# Aux_Board_V4.net
KiCad netlist of a schematic drawn in EAGLE
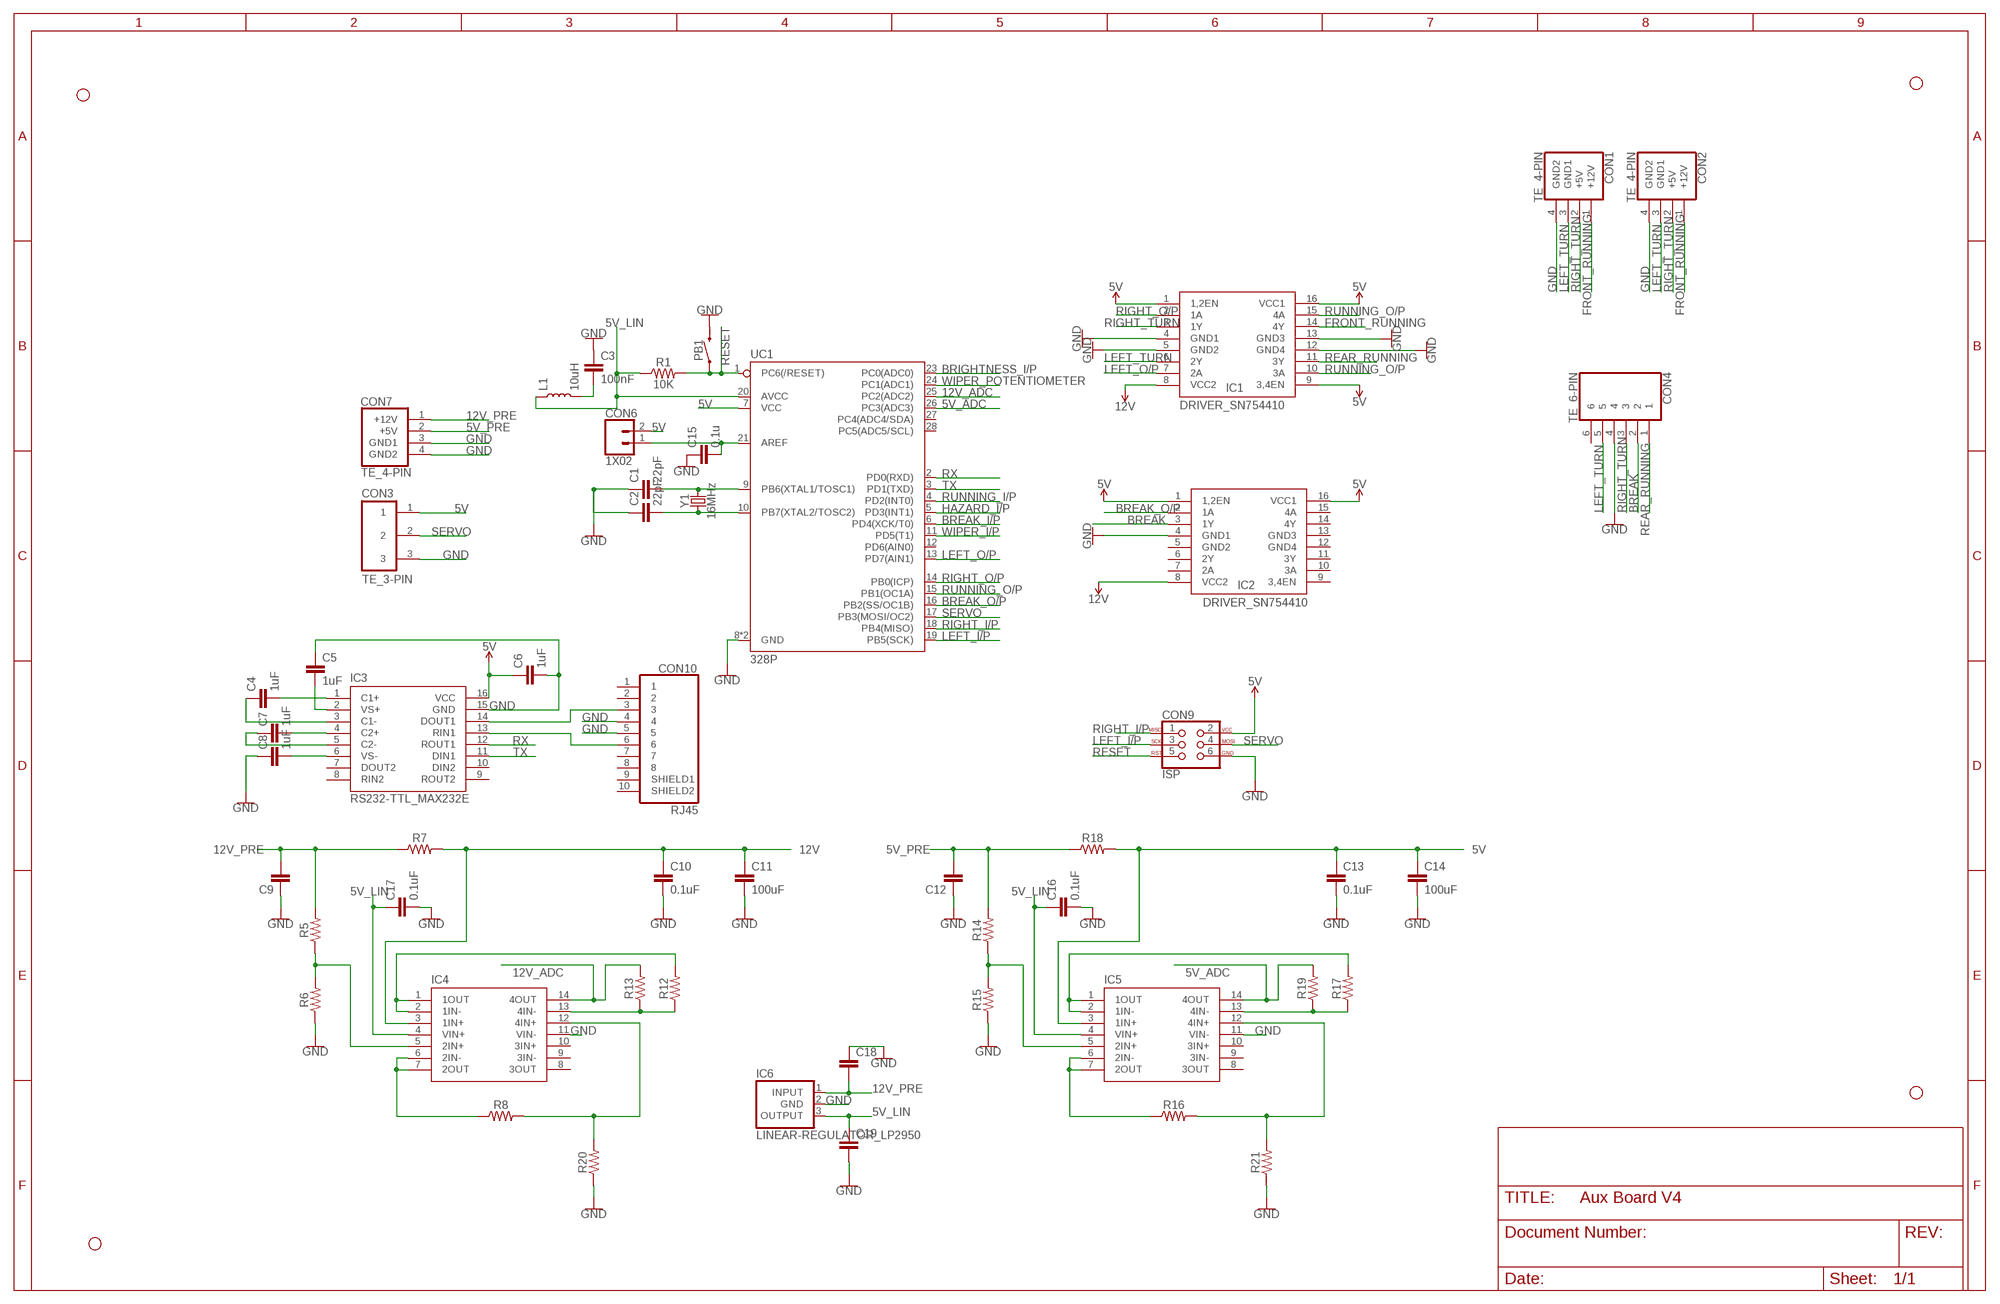
[diagram p0: schematic, sheet 1]

(export (version "E")
  (design (tool "Eeschema 10.0.6"))
  (components
    (comp (ref "C1")
      (value "22pF")
      (footprint "eagle-import:0805")
      (libsource (lib "eagle-import") (part "CAPACITOR_0805"))
    )
    (comp (ref "C2")
      (value "22pF")
      (footprint "eagle-import:0805")
      (libsource (lib "eagle-import") (part "CAPACITOR_0805"))
    )
    (comp (ref "C3")
      (value "100nF")
      (footprint "eagle-import:0805")
      (libsource (lib "eagle-import") (part "CAPACITOR_0805"))
    )
    (comp (ref "C4")
      (value "1uF")
      (footprint "eagle-import:0805")
      (libsource (lib "eagle-import") (part "CAPACITOR_0805"))
    )
    (comp (ref "C5")
      (value "1uF")
      (footprint "eagle-import:0805")
      (libsource (lib "eagle-import") (part "CAPACITOR_0805"))
    )
    (comp (ref "C6")
      (value "1uF")
      (footprint "eagle-import:0805")
      (libsource (lib "eagle-import") (part "CAPACITOR_0805"))
    )
    (comp (ref "C7")
      (value "1uF")
      (footprint "eagle-import:0805")
      (libsource (lib "eagle-import") (part "CAPACITOR_0805"))
    )
    (comp (ref "C8")
      (value "1uF")
      (footprint "eagle-import:0805")
      (libsource (lib "eagle-import") (part "CAPACITOR_0805"))
    )
    (comp (ref "C9")
      (value "CAPACITOR_0805")
      (footprint "eagle-import:0805")
      (libsource (lib "eagle-import") (part "CAPACITOR_0805"))
    )
    (comp (ref "C10")
      (value "0.1uF")
      (footprint "eagle-import:0805")
      (libsource (lib "eagle-import") (part "CAPACITOR_0805"))
    )
    (comp (ref "C11")
      (value "100uF")
      (footprint "eagle-import:0805")
      (libsource (lib "eagle-import") (part "CAPACITOR_0805"))
    )
    (comp (ref "C12")
      (value "CAPACITOR_0805")
      (footprint "eagle-import:0805")
      (libsource (lib "eagle-import") (part "CAPACITOR_0805"))
    )
    (comp (ref "C13")
      (value "0.1uF")
      (footprint "eagle-import:0805")
      (libsource (lib "eagle-import") (part "CAPACITOR_0805"))
    )
    (comp (ref "C14")
      (value "100uF")
      (footprint "eagle-import:0805")
      (libsource (lib "eagle-import") (part "CAPACITOR_0805"))
    )
    (comp (ref "C15")
      (value "0.1u")
      (footprint "eagle-import:0805")
      (libsource (lib "eagle-import") (part "CAPACITOR_0805"))
    )
    (comp (ref "C16")
      (value "0.1uF")
      (footprint "eagle-import:0805")
      (libsource (lib "eagle-import") (part "CAPACITOR_0805"))
    )
    (comp (ref "C17")
      (value "0.1uF")
      (footprint "eagle-import:0805")
      (libsource (lib "eagle-import") (part "CAPACITOR_0805"))
    )
    (comp (ref "C18")
      (value "CAPACITOR_0805")
      (footprint "eagle-import:0805")
      (libsource (lib "eagle-import") (part "CAPACITOR_0805"))
    )
    (comp (ref "C19")
      (value "CAPACITOR_0805")
      (footprint "eagle-import:0805")
      (libsource (lib "eagle-import") (part "CAPACITOR_0805"))
    )
    (comp (ref "CON1")
      (value "TE_4-PIN")
      (footprint "eagle-import:TE_4-PIN")
      (libsource (lib "eagle-import") (part "TE_4-PIN"))
    )
    (comp (ref "CON2")
      (value "TE_4-PIN")
      (footprint "eagle-import:TE_4-PIN")
      (libsource (lib "eagle-import") (part "TE_4-PIN"))
    )
    (comp (ref "CON3")
      (value "TE_3-PIN")
      (footprint "eagle-import:TE_3-PIN")
      (libsource (lib "eagle-import") (part "TE_3-PIN"))
    )
    (comp (ref "CON4")
      (value "TE_6-PIN")
      (footprint "eagle-import:TE_6-PIN")
      (libsource (lib "eagle-import") (part "TE_6-PIN"))
    )
    (comp (ref "CON6")
      (value "1X02")
      (footprint "eagle-import:1X02")
      (libsource (lib "eagle-import") (part "1X02"))
    )
    (comp (ref "CON7")
      (value "TE_4-PIN")
      (footprint "eagle-import:TE_4-PIN")
      (libsource (lib "eagle-import") (part "TE_4-PIN"))
    )
    (comp (ref "CON9")
      (value "ISP")
      (footprint "eagle-import:ISP_CONNECTOR")
      (libsource (lib "eagle-import") (part "ISP"))
    )
    (comp (ref "CON10")
      (value "RJ45")
      (footprint "eagle-import:RJ45")
      (libsource (lib "eagle-import") (part "RJ45"))
    )
    (comp (ref "H1")
      (value "STAND-OFF")
      (footprint "eagle-import:STAND-OFF")
      (libsource (lib "eagle-import") (part "STAND-OFF"))
    )
    (comp (ref "H2")
      (value "STAND-OFF")
      (footprint "eagle-import:STAND-OFF")
      (libsource (lib "eagle-import") (part "STAND-OFF"))
    )
    (comp (ref "H3")
      (value "STAND-OFF")
      (footprint "eagle-import:STAND-OFF")
      (libsource (lib "eagle-import") (part "STAND-OFF"))
    )
    (comp (ref "H4")
      (value "STAND-OFF")
      (footprint "eagle-import:STAND-OFF")
      (libsource (lib "eagle-import") (part "STAND-OFF"))
    )
    (comp (ref "IC1")
      (value "DRIVER_SN754410")
      (footprint "eagle-import:DIP16")
      (libsource (lib "eagle-import") (part "DRIVER_SN754410"))
    )
    (comp (ref "IC2")
      (value "DRIVER_SN754410")
      (footprint "eagle-import:DIP16")
      (libsource (lib "eagle-import") (part "DRIVER_SN754410"))
    )
    (comp (ref "IC3")
      (value "RS232-TTL_MAX232E")
      (footprint "eagle-import:DIP16")
      (libsource (lib "eagle-import") (part "RS232-TTL_MAX232E"))
    )
    (comp (ref "IC4")
      (value "OP-AMP_QUAD")
      (footprint "eagle-import:DIP14")
      (libsource (lib "eagle-import") (part "OP-AMP_QUAD"))
    )
    (comp (ref "IC5")
      (value "OP-AMP_QUAD")
      (footprint "eagle-import:DIP14")
      (libsource (lib "eagle-import") (part "OP-AMP_QUAD"))
    )
    (comp (ref "IC6")
      (value "LINEAR-REGULATOR_LP2950")
      (footprint "eagle-import:TO92")
      (libsource (lib "eagle-import") (part "LINEAR-REGULATOR_LP2950"))
    )
    (comp (ref "L1")
      (value "10uH")
      (footprint "eagle-import:0805")
      (libsource (lib "eagle-import") (part "INDUCTOR_0805"))
    )
    (comp (ref "PB1")
      (value "PUSHBUTTON")
      (footprint "eagle-import:PUSHBUTTON")
      (libsource (lib "eagle-import") (part "PUSHBUTTON"))
    )
    (comp (ref "R1")
      (value "10K")
      (footprint "eagle-import:0805")
      (libsource (lib "eagle-import") (part "RESISTOR_0805"))
    )
    (comp (ref "R5")
      (value "RESISTOR_0805")
      (footprint "eagle-import:0805")
      (libsource (lib "eagle-import") (part "RESISTOR_0805"))
    )
    (comp (ref "R6")
      (value "RESISTOR_0805")
      (footprint "eagle-import:0805")
      (libsource (lib "eagle-import") (part "RESISTOR_0805"))
    )
    (comp (ref "R7")
      (value "RESISTOR_1210")
      (footprint "eagle-import:1210")
      (libsource (lib "eagle-import") (part "RESISTOR_1210"))
    )
    (comp (ref "R8")
      (value "RESISTOR_0805")
      (footprint "eagle-import:0805")
      (libsource (lib "eagle-import") (part "RESISTOR_0805"))
    )
    (comp (ref "R12")
      (value "RESISTOR_0805")
      (footprint "eagle-import:0805")
      (libsource (lib "eagle-import") (part "RESISTOR_0805"))
    )
    (comp (ref "R13")
      (value "RESISTOR_0805")
      (footprint "eagle-import:0805")
      (libsource (lib "eagle-import") (part "RESISTOR_0805"))
    )
    (comp (ref "R14")
      (value "RESISTOR_0805")
      (footprint "eagle-import:0805")
      (libsource (lib "eagle-import") (part "RESISTOR_0805"))
    )
    (comp (ref "R15")
      (value "RESISTOR_0805")
      (footprint "eagle-import:0805")
      (libsource (lib "eagle-import") (part "RESISTOR_0805"))
    )
    (comp (ref "R16")
      (value "RESISTOR_0805")
      (footprint "eagle-import:0805")
      (libsource (lib "eagle-import") (part "RESISTOR_0805"))
    )
    (comp (ref "R17")
      (value "RESISTOR_0805")
      (footprint "eagle-import:0805")
      (libsource (lib "eagle-import") (part "RESISTOR_0805"))
    )
    (comp (ref "R18")
      (value "RESISTOR_1210")
      (footprint "eagle-import:1210")
      (libsource (lib "eagle-import") (part "RESISTOR_1210"))
    )
    (comp (ref "R19")
      (value "RESISTOR_0805")
      (footprint "eagle-import:0805")
      (libsource (lib "eagle-import") (part "RESISTOR_0805"))
    )
    (comp (ref "R20")
      (value "RESISTOR_0805")
      (footprint "eagle-import:0805")
      (libsource (lib "eagle-import") (part "RESISTOR_0805"))
    )
    (comp (ref "R21")
      (value "RESISTOR_0805")
      (footprint "eagle-import:0805")
      (libsource (lib "eagle-import") (part "RESISTOR_0805"))
    )
    (comp (ref "UC1")
      (value "328P")
      (footprint "eagle-import:DIP28")
      (libsource (lib "eagle-import") (part "ATMEGA328P_DIP28"))
    )
    (comp (ref "Y1")
      (value "16MHz")
      (footprint "eagle-import:HC49US")
      (libsource (lib "eagle-import") (part "CRYSTAL-16MHZPTH-HC49US"))
    )
  )
  (nets
    (net (code "1") (name "/5V_ADC") (class "Default")
      (node (ref "IC5") (pin "14") (pinfunction "4OUT_14") (pintype "bidirectional"))
      (node (ref "R19") (pin "2") (pinfunction "2_2") (pintype "passive"))
      (node (ref "UC1") (pin "26") (pinfunction "PC3(ADC3)_26") (pintype "bidirectional"))
    )
    (net (code "2") (name "/5V_LIN") (class "Default")
      (node (ref "C16") (pin "1") (pinfunction "1_1") (pintype "passive"))
      (node (ref "C17") (pin "1") (pinfunction "1_1") (pintype "passive"))
      (node (ref "C19") (pin "1") (pinfunction "1_1") (pintype "passive"))
      (node (ref "IC4") (pin "4") (pinfunction "VIN+_4") (pintype "bidirectional"))
      (node (ref "IC5") (pin "4") (pinfunction "VIN+_4") (pintype "bidirectional"))
      (node (ref "IC6") (pin "3") (pinfunction "OUTPUT_3") (pintype "bidirectional"))
      (node (ref "L1") (pin "1") (pinfunction "1_1") (pintype "passive"))
      (node (ref "R1") (pin "1") (pinfunction "1_1") (pintype "passive"))
      (node (ref "UC1") (pin "20") (pinfunction "AVCC_20") (pintype "bidirectional"))
    )
    (net (code "3") (name "/5V_PRE") (class "Default")
      (node (ref "C12") (pin "2") (pinfunction "2_2") (pintype "passive"))
      (node (ref "CON7") (pin "2") (pinfunction "+5V_2") (pintype "passive"))
      (node (ref "R14") (pin "2") (pinfunction "2_2") (pintype "passive"))
      (node (ref "R18") (pin "1") (pinfunction "1_1") (pintype "passive"))
    )
    (net (code "4") (name "/12V_ADC") (class "Default")
      (node (ref "IC4") (pin "14") (pinfunction "4OUT_14") (pintype "bidirectional"))
      (node (ref "R13") (pin "2") (pinfunction "2_2") (pintype "passive"))
      (node (ref "UC1") (pin "25") (pinfunction "PC2(ADC2)_25") (pintype "bidirectional"))
    )
    (net (code "5") (name "/12V_PRE") (class "Default")
      (node (ref "C18") (pin "2") (pinfunction "2_2") (pintype "passive"))
      (node (ref "C9") (pin "2") (pinfunction "2_2") (pintype "passive"))
      (node (ref "CON7") (pin "1") (pinfunction "+12V_1") (pintype "passive"))
      (node (ref "IC6") (pin "1") (pinfunction "INPUT_1") (pintype "bidirectional"))
      (node (ref "R5") (pin "2") (pinfunction "2_2") (pintype "passive"))
      (node (ref "R7") (pin "1") (pinfunction "1_1") (pintype "passive"))
    )
    (net (code "6") (name "/BREAK") (class "Default")
      (node (ref "CON4") (pin "2") (pinfunction "2_2") (pintype "passive"))
      (node (ref "IC2") (pin "3") (pinfunction "1Y_3") (pintype "bidirectional"))
    )
    (net (code "7") (name "/BREAK_I{slash}P") (class "Default")
      (node (ref "UC1") (pin "6") (pinfunction "PD4(XCK/T0)_6") (pintype "bidirectional"))
    )
    (net (code "8") (name "/BREAK_O{slash}P") (class "Default")
      (node (ref "IC2") (pin "2") (pinfunction "1A_2") (pintype "bidirectional"))
      (node (ref "UC1") (pin "16") (pinfunction "PB2(SS/OC1B)_16") (pintype "bidirectional"))
    )
    (net (code "9") (name "/BRIGHTNESS_I{slash}P") (class "Default")
      (node (ref "UC1") (pin "23") (pinfunction "PC0(ADC0)_23") (pintype "bidirectional"))
    )
    (net (code "10") (name "/FRONT_RUNNING") (class "Default")
      (node (ref "CON1") (pin "1") (pinfunction "+12V_1") (pintype "passive"))
      (node (ref "CON2") (pin "1") (pinfunction "+12V_1") (pintype "passive"))
      (node (ref "IC1") (pin "14") (pinfunction "4Y_14") (pintype "bidirectional"))
    )
    (net (code "11") (name "/HAZARD_I{slash}P") (class "Default")
      (node (ref "UC1") (pin "5") (pinfunction "PD3(INT1)_5") (pintype "bidirectional"))
    )
    (net (code "12") (name "/LEFT_I{slash}P") (class "Default")
      (node (ref "CON9") (pin "3") (pinfunction "3_3") (pintype "passive"))
      (node (ref "UC1") (pin "19") (pinfunction "PB5(SCK)_19") (pintype "bidirectional"))
    )
    (net (code "13") (name "/LEFT_O{slash}P") (class "Default")
      (node (ref "IC1") (pin "7") (pinfunction "2A_7") (pintype "bidirectional"))
      (node (ref "UC1") (pin "13") (pinfunction "PD7(AIN1)_13") (pintype "bidirectional"))
    )
    (net (code "14") (name "/LEFT_TURN") (class "Default")
      (node (ref "CON1") (pin "3") (pinfunction "GND1_3") (pintype "passive"))
      (node (ref "CON2") (pin "3") (pinfunction "GND1_3") (pintype "passive"))
      (node (ref "CON4") (pin "5") (pinfunction "5_5") (pintype "passive"))
      (node (ref "IC1") (pin "6") (pinfunction "2Y_6") (pintype "bidirectional"))
    )
    (net (code "15") (name "/REAR_RUNNING") (class "Default")
      (node (ref "CON4") (pin "1") (pinfunction "1_1") (pintype "passive"))
      (node (ref "IC1") (pin "11") (pinfunction "3Y_11") (pintype "bidirectional"))
    )
    (net (code "16") (name "/RESET") (class "Default")
      (node (ref "CON9") (pin "5") (pinfunction "5_5") (pintype "passive"))
      (node (ref "PB1") (pin "1") (pinfunction "1_1") (pintype "passive"))
      (node (ref "PB1") (pin "2") (pinfunction "1_2") (pintype "passive"))
      (node (ref "R1") (pin "2") (pinfunction "2_2") (pintype "passive"))
      (node (ref "UC1") (pin "1") (pinfunction "PC6(/RESET)_1") (pintype "bidirectional"))
    )
    (net (code "17") (name "/RIGHT_I{slash}P") (class "Default")
      (node (ref "CON9") (pin "1") (pinfunction "1_1") (pintype "passive"))
      (node (ref "UC1") (pin "18") (pinfunction "PB4(MISO)_18") (pintype "bidirectional"))
    )
    (net (code "18") (name "/RIGHT_O{slash}P") (class "Default")
      (node (ref "IC1") (pin "2") (pinfunction "1A_2") (pintype "bidirectional"))
      (node (ref "UC1") (pin "14") (pinfunction "PB0(ICP)_14") (pintype "bidirectional"))
    )
    (net (code "19") (name "/RIGHT_TURN") (class "Default")
      (node (ref "CON1") (pin "2") (pinfunction "+5V_2") (pintype "passive"))
      (node (ref "CON2") (pin "2") (pinfunction "+5V_2") (pintype "passive"))
      (node (ref "CON4") (pin "3") (pinfunction "3_3") (pintype "passive"))
      (node (ref "IC1") (pin "3") (pinfunction "1Y_3") (pintype "bidirectional"))
    )
    (net (code "20") (name "/RUNNING_I{slash}P") (class "Default")
      (node (ref "UC1") (pin "4") (pinfunction "PD2(INT0)_4") (pintype "bidirectional"))
    )
    (net (code "21") (name "/RUNNING_O{slash}P") (class "Default")
      (node (ref "IC1") (pin "10") (pinfunction "3A_10") (pintype "bidirectional"))
      (node (ref "IC1") (pin "15") (pinfunction "4A_15") (pintype "bidirectional"))
      (node (ref "UC1") (pin "15") (pinfunction "PB1(OC1A)_15") (pintype "bidirectional"))
    )
    (net (code "22") (name "/RX") (class "Default")
      (node (ref "IC3") (pin "12") (pinfunction "ROUT1_12") (pintype "bidirectional"))
      (node (ref "UC1") (pin "2") (pinfunction "PD0(RXD)_2") (pintype "bidirectional"))
    )
    (net (code "23") (name "/SERVO") (class "Default")
      (node (ref "CON3") (pin "2") (pinfunction "2_2") (pintype "passive"))
      (node (ref "CON9") (pin "4") (pinfunction "4_4") (pintype "passive"))
      (node (ref "UC1") (pin "17") (pinfunction "PB3(MOSI/OC2)_17") (pintype "bidirectional"))
    )
    (net (code "24") (name "/TX") (class "Default")
      (node (ref "IC3") (pin "11") (pinfunction "DIN1_11") (pintype "bidirectional"))
      (node (ref "UC1") (pin "3") (pinfunction "PD1(TXD)_3") (pintype "bidirectional"))
    )
    (net (code "25") (name "/WIPER_I{slash}P") (class "Default")
      (node (ref "UC1") (pin "11") (pinfunction "PD5(T1)_11") (pintype "bidirectional"))
    )
    (net (code "26") (name "/WIPER_POTENTIOMETER") (class "Default")
      (node (ref "UC1") (pin "24") (pinfunction "PC1(ADC1)_24") (pintype "bidirectional"))
    )
    (net (code "27") (name "5V") (class "Default")
      (node (ref "C13") (pin "1") (pinfunction "1_1") (pintype "passive"))
      (node (ref "C14") (pin "1") (pinfunction "1_1") (pintype "passive"))
      (node (ref "C15") (pin "2") (pinfunction "2_2") (pintype "passive"))
      (node (ref "C6") (pin "1") (pinfunction "1_1") (pintype "passive"))
      (node (ref "CON3") (pin "1") (pinfunction "1_1") (pintype "passive"))
      (node (ref "CON6") (pin "1") (pinfunction "1_1") (pintype "passive"))
      (node (ref "CON6") (pin "2") (pinfunction "2_2") (pintype "passive"))
      (node (ref "CON9") (pin "2") (pinfunction "2_2") (pintype "passive"))
      (node (ref "IC1") (pin "1") (pinfunction "1,2EN_1") (pintype "bidirectional"))
      (node (ref "IC1") (pin "16") (pinfunction "VCC1_16") (pintype "bidirectional"))
      (node (ref "IC1") (pin "9") (pinfunction "3,4EN_9") (pintype "bidirectional"))
      (node (ref "IC2") (pin "1") (pinfunction "1,2EN_1") (pintype "bidirectional"))
      (node (ref "IC2") (pin "16") (pinfunction "VCC1_16") (pintype "bidirectional"))
      (node (ref "IC3") (pin "16") (pinfunction "VCC_16") (pintype "bidirectional"))
      (node (ref "IC5") (pin "3") (pinfunction "1IN+_3") (pintype "bidirectional"))
      (node (ref "R18") (pin "2") (pinfunction "2_2") (pintype "passive"))
      (node (ref "UC1") (pin "21") (pinfunction "AREF_21") (pintype "bidirectional"))
      (node (ref "UC1") (pin "7") (pinfunction "VCC_7") (pintype "bidirectional"))
    )
    (net (code "28") (name "12V") (class "Default")
      (node (ref "C10") (pin "1") (pinfunction "1_1") (pintype "passive"))
      (node (ref "C11") (pin "1") (pinfunction "1_1") (pintype "passive"))
      (node (ref "IC1") (pin "8") (pinfunction "VCC2_8") (pintype "bidirectional"))
      (node (ref "IC2") (pin "8") (pinfunction "VCC2_8") (pintype "bidirectional"))
      (node (ref "IC4") (pin "3") (pinfunction "1IN+_3") (pintype "bidirectional"))
      (node (ref "R7") (pin "2") (pinfunction "2_2") (pintype "passive"))
    )
    (net (code "29") (name "GND") (class "Default")
      (node (ref "C1") (pin "1") (pinfunction "1_1") (pintype "passive"))
      (node (ref "C10") (pin "2") (pinfunction "2_2") (pintype "passive"))
      (node (ref "C11") (pin "2") (pinfunction "2_2") (pintype "passive"))
      (node (ref "C12") (pin "1") (pinfunction "1_1") (pintype "passive"))
      (node (ref "C13") (pin "2") (pinfunction "2_2") (pintype "passive"))
      (node (ref "C14") (pin "2") (pinfunction "2_2") (pintype "passive"))
      (node (ref "C15") (pin "1") (pinfunction "1_1") (pintype "passive"))
      (node (ref "C16") (pin "2") (pinfunction "2_2") (pintype "passive"))
      (node (ref "C17") (pin "2") (pinfunction "2_2") (pintype "passive"))
      (node (ref "C18") (pin "1") (pinfunction "1_1") (pintype "passive"))
      (node (ref "C19") (pin "2") (pinfunction "2_2") (pintype "passive"))
      (node (ref "C2") (pin "1") (pinfunction "1_1") (pintype "passive"))
      (node (ref "C3") (pin "1") (pinfunction "1_1") (pintype "passive"))
      (node (ref "C5") (pin "1") (pinfunction "1_1") (pintype "passive"))
      (node (ref "C6") (pin "2") (pinfunction "2_2") (pintype "passive"))
      (node (ref "C8") (pin "1") (pinfunction "1_1") (pintype "passive"))
      (node (ref "C9") (pin "1") (pinfunction "1_1") (pintype "passive"))
      (node (ref "CON1") (pin "4") (pinfunction "GND2_4") (pintype "passive"))
      (node (ref "CON10") (pin "4") (pinfunction "4_4") (pintype "passive"))
      (node (ref "CON10") (pin "5") (pinfunction "5_5") (pintype "passive"))
      (node (ref "CON2") (pin "4") (pinfunction "GND2_4") (pintype "passive"))
      (node (ref "CON3") (pin "3") (pinfunction "3_3") (pintype "passive"))
      (node (ref "CON4") (pin "4") (pinfunction "4_4") (pintype "passive"))
      (node (ref "CON7") (pin "3") (pinfunction "GND1_3") (pintype "passive"))
      (node (ref "CON7") (pin "4") (pinfunction "GND2_4") (pintype "passive"))
      (node (ref "CON9") (pin "6") (pinfunction "6_6") (pintype "passive"))
      (node (ref "IC1") (pin "12") (pinfunction "GND4_12") (pintype "bidirectional"))
      (node (ref "IC1") (pin "13") (pinfunction "GND3_13") (pintype "bidirectional"))
      (node (ref "IC1") (pin "4") (pinfunction "GND1_4") (pintype "bidirectional"))
      (node (ref "IC1") (pin "5") (pinfunction "GND2_5") (pintype "bidirectional"))
      (node (ref "IC2") (pin "4") (pinfunction "GND1_4") (pintype "bidirectional"))
      (node (ref "IC3") (pin "15") (pinfunction "GND_15") (pintype "bidirectional"))
      (node (ref "IC4") (pin "11") (pinfunction "VIN-_11") (pintype "bidirectional"))
      (node (ref "IC5") (pin "11") (pinfunction "VIN-_11") (pintype "bidirectional"))
      (node (ref "IC6") (pin "2") (pinfunction "GND_2") (pintype "bidirectional"))
      (node (ref "PB1") (pin "3") (pinfunction "2_3") (pintype "passive"))
      (node (ref "PB1") (pin "4") (pinfunction "2_4") (pintype "passive"))
      (node (ref "R15") (pin "1") (pinfunction "1_1") (pintype "passive"))
      (node (ref "R20") (pin "1") (pinfunction "1_1") (pintype "passive"))
      (node (ref "R21") (pin "1") (pinfunction "1_1") (pintype "passive"))
      (node (ref "R6") (pin "1") (pinfunction "1_1") (pintype "passive"))
      (node (ref "UC1") (pin "22") (pinfunction "GND_22") (pintype "bidirectional"))
      (node (ref "UC1") (pin "8") (pinfunction "GND_8") (pintype "bidirectional"))
    )
    (net (code "30") (name "Net-(C3-Pad2)") (class "Default")
      (node (ref "C3") (pin "2") (pinfunction "2_2") (pintype "passive"))
      (node (ref "L1") (pin "2") (pinfunction "2_2") (pintype "passive"))
    )
    (net (code "31") (name "Net-(IC3-C1+)") (class "Default")
      (node (ref "C4") (pin "2") (pinfunction "2_2") (pintype "passive"))
      (node (ref "IC3") (pin "1") (pinfunction "C1+_1") (pintype "bidirectional"))
    )
    (net (code "32") (name "Net-(IC3-C1-)") (class "Default")
      (node (ref "C4") (pin "1") (pinfunction "1_1") (pintype "passive"))
      (node (ref "IC3") (pin "3") (pinfunction "C1-_3") (pintype "bidirectional"))
    )
    (net (code "33") (name "Net-(IC3-C2+)") (class "Default")
      (node (ref "C7") (pin "2") (pinfunction "2_2") (pintype "passive"))
      (node (ref "IC3") (pin "4") (pinfunction "C2+_4") (pintype "bidirectional"))
    )
    (net (code "34") (name "Net-(IC3-C2-)") (class "Default")
      (node (ref "C7") (pin "1") (pinfunction "1_1") (pintype "passive"))
      (node (ref "IC3") (pin "5") (pinfunction "C2-_5") (pintype "bidirectional"))
    )
    (net (code "35") (name "Net-(IC3-DOUT1)") (class "Default")
      (node (ref "CON10") (pin "3") (pinfunction "3_3") (pintype "passive"))
      (node (ref "IC3") (pin "14") (pinfunction "DOUT1_14") (pintype "bidirectional"))
    )
    (net (code "36") (name "Net-(IC3-RIN1)") (class "Default")
      (node (ref "CON10") (pin "6") (pinfunction "6_6") (pintype "passive"))
      (node (ref "IC3") (pin "13") (pinfunction "RIN1_13") (pintype "bidirectional"))
    )
    (net (code "37") (name "Net-(IC3-VS+)") (class "Default")
      (node (ref "C5") (pin "2") (pinfunction "2_2") (pintype "passive"))
      (node (ref "IC3") (pin "2") (pinfunction "VS+_2") (pintype "bidirectional"))
    )
    (net (code "38") (name "Net-(IC3-VS-)") (class "Default")
      (node (ref "C8") (pin "2") (pinfunction "2_2") (pintype "passive"))
      (node (ref "IC3") (pin "6") (pinfunction "VS-_6") (pintype "bidirectional"))
    )
    (net (code "39") (name "Net-(IC4-1IN-)") (class "Default")
      (node (ref "IC4") (pin "1") (pinfunction "1OUT_1") (pintype "bidirectional"))
      (node (ref "IC4") (pin "2") (pinfunction "1IN-_2") (pintype "bidirectional"))
      (node (ref "R12") (pin "2") (pinfunction "2_2") (pintype "passive"))
    )
    (net (code "40") (name "Net-(IC4-2IN+)") (class "Default")
      (node (ref "IC4") (pin "5") (pinfunction "2IN+_5") (pintype "bidirectional"))
      (node (ref "R5") (pin "1") (pinfunction "1_1") (pintype "passive"))
      (node (ref "R6") (pin "2") (pinfunction "2_2") (pintype "passive"))
    )
    (net (code "41") (name "Net-(IC4-2IN-)") (class "Default")
      (node (ref "IC4") (pin "6") (pinfunction "2IN-_6") (pintype "bidirectional"))
      (node (ref "IC4") (pin "7") (pinfunction "2OUT_7") (pintype "bidirectional"))
      (node (ref "R8") (pin "1") (pinfunction "1_1") (pintype "passive"))
    )
    (net (code "42") (name "Net-(IC4-4IN+)") (class "Default")
      (node (ref "IC4") (pin "12") (pinfunction "4IN+_12") (pintype "bidirectional"))
      (node (ref "R20") (pin "2") (pinfunction "2_2") (pintype "passive"))
      (node (ref "R8") (pin "2") (pinfunction "2_2") (pintype "passive"))
    )
    (net (code "43") (name "Net-(IC4-4IN-)") (class "Default")
      (node (ref "IC4") (pin "13") (pinfunction "4IN-_13") (pintype "bidirectional"))
      (node (ref "R12") (pin "1") (pinfunction "1_1") (pintype "passive"))
      (node (ref "R13") (pin "1") (pinfunction "1_1") (pintype "passive"))
    )
    (net (code "44") (name "Net-(IC5-1IN-)") (class "Default")
      (node (ref "IC5") (pin "1") (pinfunction "1OUT_1") (pintype "bidirectional"))
      (node (ref "IC5") (pin "2") (pinfunction "1IN-_2") (pintype "bidirectional"))
      (node (ref "R17") (pin "2") (pinfunction "2_2") (pintype "passive"))
    )
    (net (code "45") (name "Net-(IC5-2IN+)") (class "Default")
      (node (ref "IC5") (pin "5") (pinfunction "2IN+_5") (pintype "bidirectional"))
      (node (ref "R14") (pin "1") (pinfunction "1_1") (pintype "passive"))
      (node (ref "R15") (pin "2") (pinfunction "2_2") (pintype "passive"))
    )
    (net (code "46") (name "Net-(IC5-2IN-)") (class "Default")
      (node (ref "IC5") (pin "6") (pinfunction "2IN-_6") (pintype "bidirectional"))
      (node (ref "IC5") (pin "7") (pinfunction "2OUT_7") (pintype "bidirectional"))
      (node (ref "R16") (pin "1") (pinfunction "1_1") (pintype "passive"))
    )
    (net (code "47") (name "Net-(IC5-4IN+)") (class "Default")
      (node (ref "IC5") (pin "12") (pinfunction "4IN+_12") (pintype "bidirectional"))
      (node (ref "R16") (pin "2") (pinfunction "2_2") (pintype "passive"))
      (node (ref "R21") (pin "2") (pinfunction "2_2") (pintype "passive"))
    )
    (net (code "48") (name "Net-(IC5-4IN-)") (class "Default")
      (node (ref "IC5") (pin "13") (pinfunction "4IN-_13") (pintype "bidirectional"))
      (node (ref "R17") (pin "1") (pinfunction "1_1") (pintype "passive"))
      (node (ref "R19") (pin "1") (pinfunction "1_1") (pintype "passive"))
    )
    (net (code "49") (name "Net-(UC1-PB6(XTAL1{slash}TOSC1))") (class "Default")
      (node (ref "C1") (pin "2") (pinfunction "2_2") (pintype "passive"))
      (node (ref "UC1") (pin "9") (pinfunction "PB6(XTAL1/TOSC1)_9") (pintype "bidirectional"))
      (node (ref "Y1") (pin "2") (pinfunction "2_2") (pintype "passive"))
    )
    (net (code "50") (name "Net-(UC1-PB7(XTAL2{slash}TOSC2))") (class "Default")
      (node (ref "C2") (pin "2") (pinfunction "2_2") (pintype "passive"))
      (node (ref "UC1") (pin "10") (pinfunction "PB7(XTAL2/TOSC2)_10") (pintype "bidirectional"))
      (node (ref "Y1") (pin "1") (pinfunction "1_1") (pintype "passive"))
    )
    (net (code "51") (name "unconnected-(CON4-Pad6)") (class "Default")
      (node (ref "CON4") (pin "6") (pinfunction "6_6") (pintype "passive"))
    )
    (net (code "52") (name "unconnected-(CON10-Pad1)") (class "Default")
      (node (ref "CON10") (pin "1") (pinfunction "1_1") (pintype "passive"))
    )
    (net (code "53") (name "unconnected-(CON10-Pad2)") (class "Default")
      (node (ref "CON10") (pin "2") (pinfunction "2_2") (pintype "passive"))
    )
    (net (code "54") (name "unconnected-(CON10-Pad7)") (class "Default")
      (node (ref "CON10") (pin "7") (pinfunction "7_7") (pintype "passive"))
    )
    (net (code "55") (name "unconnected-(CON10-Pad8)") (class "Default")
      (node (ref "CON10") (pin "8") (pinfunction "8_8") (pintype "passive"))
    )
    (net (code "56") (name "unconnected-(CON10-SHIELD1-Pad9)") (class "Default")
      (node (ref "CON10") (pin "9") (pinfunction "SHIELD1_9") (pintype "passive"))
    )
    (net (code "57") (name "unconnected-(CON10-SHIELD2-Pad10)") (class "Default")
      (node (ref "CON10") (pin "10") (pinfunction "SHIELD2_10") (pintype "passive"))
    )
    (net (code "58") (name "unconnected-(IC2-2A-Pad7)") (class "Default")
      (node (ref "IC2") (pin "7") (pinfunction "2A_7") (pintype "bidirectional"))
    )
    (net (code "59") (name "unconnected-(IC2-2Y-Pad6)") (class "Default")
      (node (ref "IC2") (pin "6") (pinfunction "2Y_6") (pintype "bidirectional"))
    )
    (net (code "60") (name "unconnected-(IC2-3,4EN-Pad9)") (class "Default")
      (node (ref "IC2") (pin "9") (pinfunction "3,4EN_9") (pintype "bidirectional"))
    )
    (net (code "61") (name "unconnected-(IC2-3A-Pad10)") (class "Default")
      (node (ref "IC2") (pin "10") (pinfunction "3A_10") (pintype "bidirectional"))
    )
    (net (code "62") (name "unconnected-(IC2-3Y-Pad11)") (class "Default")
      (node (ref "IC2") (pin "11") (pinfunction "3Y_11") (pintype "bidirectional"))
    )
    (net (code "63") (name "unconnected-(IC2-4A-Pad15)") (class "Default")
      (node (ref "IC2") (pin "15") (pinfunction "4A_15") (pintype "bidirectional"))
    )
    (net (code "64") (name "unconnected-(IC2-4Y-Pad14)") (class "Default")
      (node (ref "IC2") (pin "14") (pinfunction "4Y_14") (pintype "bidirectional"))
    )
    (net (code "65") (name "unconnected-(IC2-GND2-Pad5)") (class "Default")
      (node (ref "IC2") (pin "5") (pinfunction "GND2_5") (pintype "bidirectional"))
    )
    (net (code "66") (name "unconnected-(IC2-GND3-Pad13)") (class "Default")
      (node (ref "IC2") (pin "13") (pinfunction "GND3_13") (pintype "bidirectional"))
    )
    (net (code "67") (name "unconnected-(IC2-GND4-Pad12)") (class "Default")
      (node (ref "IC2") (pin "12") (pinfunction "GND4_12") (pintype "bidirectional"))
    )
    (net (code "68") (name "unconnected-(IC3-DIN2-Pad10)") (class "Default")
      (node (ref "IC3") (pin "10") (pinfunction "DIN2_10") (pintype "bidirectional"))
    )
    (net (code "69") (name "unconnected-(IC3-DOUT2-Pad7)") (class "Default")
      (node (ref "IC3") (pin "7") (pinfunction "DOUT2_7") (pintype "bidirectional"))
    )
    (net (code "70") (name "unconnected-(IC3-RIN2-Pad8)") (class "Default")
      (node (ref "IC3") (pin "8") (pinfunction "RIN2_8") (pintype "bidirectional"))
    )
    (net (code "71") (name "unconnected-(IC3-ROUT2-Pad9)") (class "Default")
      (node (ref "IC3") (pin "9") (pinfunction "ROUT2_9") (pintype "bidirectional"))
    )
    (net (code "72") (name "unconnected-(IC4-3IN+-Pad10)") (class "Default")
      (node (ref "IC4") (pin "10") (pinfunction "3IN+_10") (pintype "bidirectional"))
    )
    (net (code "73") (name "unconnected-(IC4-3IN--Pad9)") (class "Default")
      (node (ref "IC4") (pin "9") (pinfunction "3IN-_9") (pintype "bidirectional"))
    )
    (net (code "74") (name "unconnected-(IC4-3OUT-Pad8)") (class "Default")
      (node (ref "IC4") (pin "8") (pinfunction "3OUT_8") (pintype "bidirectional"))
    )
    (net (code "75") (name "unconnected-(IC5-3IN+-Pad10)") (class "Default")
      (node (ref "IC5") (pin "10") (pinfunction "3IN+_10") (pintype "bidirectional"))
    )
    (net (code "76") (name "unconnected-(IC5-3IN--Pad9)") (class "Default")
      (node (ref "IC5") (pin "9") (pinfunction "3IN-_9") (pintype "bidirectional"))
    )
    (net (code "77") (name "unconnected-(IC5-3OUT-Pad8)") (class "Default")
      (node (ref "IC5") (pin "8") (pinfunction "3OUT_8") (pintype "bidirectional"))
    )
    (net (code "78") (name "unconnected-(UC1-PC4(ADC4{slash}SDA)-Pad27)") (class "Default")
      (node (ref "UC1") (pin "27") (pinfunction "PC4(ADC4/SDA)_27") (pintype "bidirectional"))
    )
    (net (code "79") (name "unconnected-(UC1-PC5(ADC5{slash}SCL)-Pad28)") (class "Default")
      (node (ref "UC1") (pin "28") (pinfunction "PC5(ADC5/SCL)_28") (pintype "bidirectional"))
    )
    (net (code "80") (name "unconnected-(UC1-PD6(AIN0)-Pad12)") (class "Default")
      (node (ref "UC1") (pin "12") (pinfunction "PD6(AIN0)_12") (pintype "bidirectional"))
    )
  )
)
